# power_sup_basic.net
KiCad netlist of a schematic drawn in EAGLE
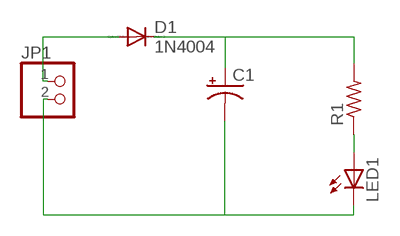
[diagram p0: schematic, sheet 1]

(export (version "E")
  (design (tool "Eeschema 10.0.6"))
  (components
    (comp (ref "C1")
      (value "CPOL-USE3.5-10")
      (footprint "eagle-import:E3,5-10")
      (libsource (lib "eagle-import") (part "CPOL-USE3.5-10"))
    )
    (comp (ref "D1")
      (value "1N4004")
      (footprint "eagle-import:DO41-10")
      (libsource (lib "eagle-import") (part "1N4004"))
    )
    (comp (ref "JP1")
      (value "PINHD-1X2")
      (footprint "eagle-import:1X02")
      (libsource (lib "eagle-import") (part "PINHD-1X2"))
    )
    (comp (ref "LED1")
      (value "LED5MM")
      (footprint "eagle-import:LED5MM")
      (libsource (lib "eagle-import") (part "LED5MM"))
    )
    (comp (ref "R1")
      (value "R-US_0207/10")
      (footprint "eagle-import:0207_10")
      (libsource (lib "eagle-import") (part "R-US_0207/10"))
    )
  )
  (nets
    (net (code "1") (name "Net-(C1-Pad+)") (class "Default")
      (node (ref "C1") (pin "+") (pinfunction "+_+") (pintype "passive"))
      (node (ref "D1") (pin "C") (pinfunction "C_C") (pintype "passive"))
      (node (ref "R1") (pin "2") (pinfunction "2_2") (pintype "passive"))
    )
    (net (code "2") (name "Net-(D1-PadA)") (class "Default")
      (node (ref "D1") (pin "A") (pinfunction "A_A") (pintype "passive"))
      (node (ref "JP1") (pin "1") (pinfunction "1_1") (pintype "passive"))
    )
    (net (code "3") (name "Net-(LED1-C)") (class "Default")
      (node (ref "C1") (pin "-") (pinfunction "-_-") (pintype "passive"))
      (node (ref "JP1") (pin "2") (pinfunction "2_2") (pintype "passive"))
      (node (ref "LED1") (pin "K") (pinfunction "C_K") (pintype "passive"))
    )
    (net (code "4") (name "Net-(LED1-PadA)") (class "Default")
      (node (ref "LED1") (pin "A") (pinfunction "A_A") (pintype "passive"))
      (node (ref "R1") (pin "1") (pinfunction "1_1") (pintype "passive"))
    )
  )
)
